# Connector.net
KiCad netlist of a schematic drawn in Altium Designer
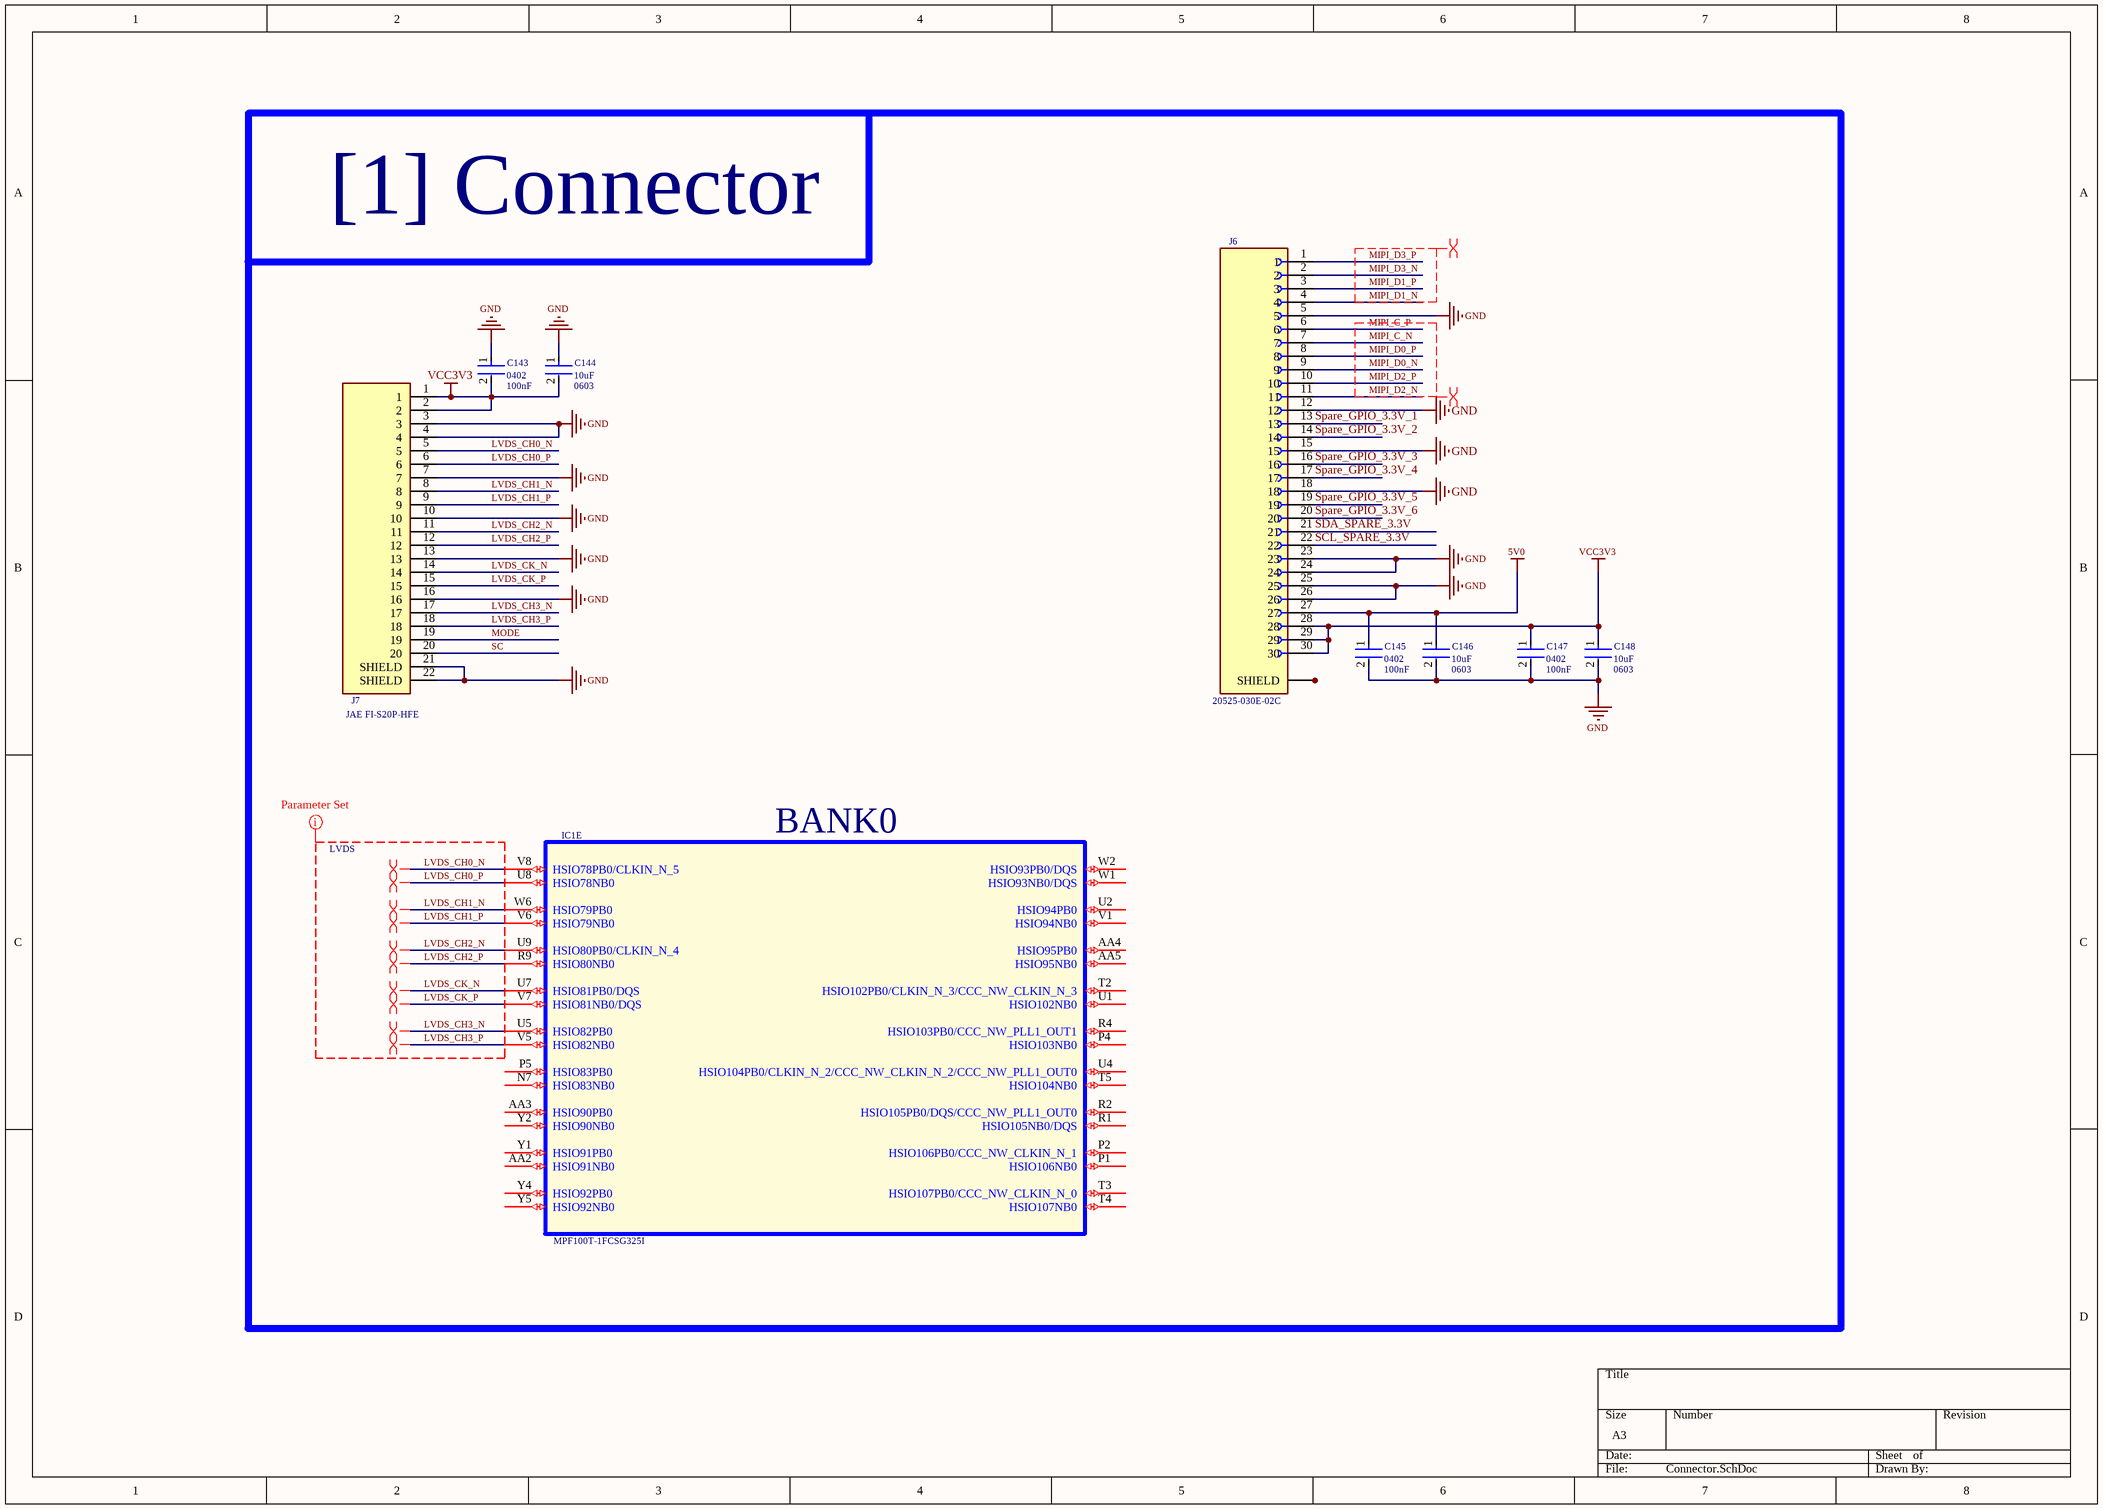
[diagram p0: Connector.SchDoc]

(export (version "E")
  (design (tool "Eeschema 10.0.6"))
  (components
    (comp (ref "C143")
      (value "C0402C104K8PACTU")
      (footprint "FP-C0402-BB-MFG")
      (description "CAP CER 0.1UF 10V X5R 0402")
      (fields
        (field (name "MANUFACTURER") "Kemet")
        (field (name "TOLERANCE") "0.1")
        (field (name "PACKAGE") "0402")
        (field (name "CAPACITANCE") "100nF")
      )
      (libsource (lib "Camera_PCB_proj") (part "CMP-2008-02046-2"))
    )
    (comp (ref "C144")
      (value "GRM188R60J106ME47D")
      (footprint "FP-GRM188-0_1-e0_2_0_55-IPC_A")
      (description "Chip Multilayer Ceramic Capacitors for General Purpose, 0603, 10uF, X5R, 15%, 20%, 6.3V")
      (fields
        (field (name "VOLTAGE") "6.3V")
        (field (name "TOLERANCE") "20%")
        (field (name "CAPACITANCE") "10uF")
        (field (name "CASE/PACKAGE") "0603")
      )
      (libsource (lib "Camera_PCB_proj") (part "CMP-2006-02792-2"))
    )
    (comp (ref "C145")
      (value "C0402C104K8PACTU")
      (footprint "FP-C0402-BB-MFG")
      (description "CAP CER 0.1UF 10V X5R 0402")
      (fields
        (field (name "MANUFACTURER") "Kemet")
        (field (name "TOLERANCE") "0.1")
        (field (name "PACKAGE") "0402")
        (field (name "CAPACITANCE") "100nF")
      )
      (libsource (lib "Camera_PCB_proj") (part "CMP-2008-02046-2"))
    )
    (comp (ref "C146")
      (value "GRM188R60J106ME47D")
      (footprint "FP-GRM188-0_1-e0_2_0_55-IPC_A")
      (description "Chip Multilayer Ceramic Capacitors for General Purpose, 0603, 10uF, X5R, 15%, 20%, 6.3V")
      (fields
        (field (name "VOLTAGE") "6.3V")
        (field (name "TOLERANCE") "20%")
        (field (name "CAPACITANCE") "10uF")
        (field (name "CASE/PACKAGE") "0603")
      )
      (libsource (lib "Camera_PCB_proj") (part "CMP-2006-02792-2"))
    )
    (comp (ref "C147")
      (value "C0402C104K8PACTU")
      (footprint "FP-C0402-BB-MFG")
      (description "CAP CER 0.1UF 10V X5R 0402")
      (fields
        (field (name "MANUFACTURER") "Kemet")
        (field (name "TOLERANCE") "0.1")
        (field (name "PACKAGE") "0402")
        (field (name "CAPACITANCE") "100nF")
      )
      (libsource (lib "Camera_PCB_proj") (part "CMP-2008-02046-2"))
    )
    (comp (ref "C148")
      (value "GRM188R60J106ME47D")
      (footprint "FP-GRM188-0_1-e0_2_0_55-IPC_A")
      (description "Chip Multilayer Ceramic Capacitors for General Purpose, 0603, 10uF, X5R, 15%, 20%, 6.3V")
      (fields
        (field (name "VOLTAGE") "6.3V")
        (field (name "TOLERANCE") "20%")
        (field (name "CAPACITANCE") "10uF")
        (field (name "CASE/PACKAGE") "0603")
      )
      (libsource (lib "Camera_PCB_proj") (part "CMP-2006-02792-2"))
    )
    (comp (ref "IC1")
      (value "MPF100T-1FCSG325I")
      (footprint "MPF100T-1FCSG325I")
      (fields (field (name "PART_NUMBER") "J00001"))
      (libsource (lib "PCB_Display_Doru") (part "MPF100T-1FCSG325I"))
    )
    (comp (ref "J6")
      (value "20525-030E-02C")
      (footprint "I-PEX_20525-030E-02C")
      (description "0.4 mm pitch, Horizontal mating Micro-coaxial cable connector")
      (fields (field (name "MF") "I-PEX"))
      (libsource (lib "Camera_PCB_proj") (part "20525-030E-02C"))
    )
    (comp (ref "J7")
      (value "JAE FI-S20P-HFE")
      (footprint "JAE FI-S20P-HFE")
      (fields (field (name "PART_NUMBER") "J00001"))
      (libsource (lib "PCB_Display_Doru") (part "JAE FI-S20P-HFE"))
    )
  )
  (nets
    (net (code "1") (name "/LVDS_CH0_N") (class "Default")
      (node (ref "IC1") (pin "V8") (pinfunction "HSIO78PB0/CLKIN_N_5_V8") (pintype "bidirectional"))
      (node (ref "J7") (pin "5") (pinfunction "5_5") (pintype "passive"))
    )
    (net (code "2") (name "/LVDS_CH0_P") (class "Default")
      (node (ref "IC1") (pin "U8") (pinfunction "HSIO78NB0_U8") (pintype "bidirectional"))
      (node (ref "J7") (pin "6") (pinfunction "6_6") (pintype "passive"))
    )
    (net (code "3") (name "/LVDS_CH1_N") (class "Default")
      (node (ref "IC1") (pin "W6") (pinfunction "HSIO79PB0_W6") (pintype "bidirectional"))
      (node (ref "J7") (pin "8") (pinfunction "8_8") (pintype "passive"))
    )
    (net (code "4") (name "/LVDS_CH1_P") (class "Default")
      (node (ref "IC1") (pin "V6") (pinfunction "HSIO79NB0_V6") (pintype "bidirectional"))
      (node (ref "J7") (pin "9") (pinfunction "9_9") (pintype "passive"))
    )
    (net (code "5") (name "/LVDS_CH2_N") (class "Default")
      (node (ref "IC1") (pin "U9") (pinfunction "HSIO80PB0/CLKIN_N_4_U9") (pintype "bidirectional"))
      (node (ref "J7") (pin "11") (pinfunction "11_11") (pintype "passive"))
    )
    (net (code "6") (name "/LVDS_CH2_P") (class "Default")
      (node (ref "IC1") (pin "R9") (pinfunction "HSIO80NB0_R9") (pintype "bidirectional"))
      (node (ref "J7") (pin "12") (pinfunction "12_12") (pintype "passive"))
    )
    (net (code "7") (name "/LVDS_CH3_N") (class "Default")
      (node (ref "IC1") (pin "U5") (pinfunction "HSIO82PB0_U5") (pintype "bidirectional"))
      (node (ref "J7") (pin "17") (pinfunction "17_17") (pintype "passive"))
    )
    (net (code "8") (name "/LVDS_CH3_P") (class "Default")
      (node (ref "IC1") (pin "V5") (pinfunction "HSIO82NB0_V5") (pintype "bidirectional"))
      (node (ref "J7") (pin "18") (pinfunction "18_18") (pintype "passive"))
    )
    (net (code "9") (name "/LVDS_CK_N") (class "Default")
      (node (ref "IC1") (pin "U7") (pinfunction "HSIO81PB0/DQS_U7") (pintype "bidirectional"))
      (node (ref "J7") (pin "14") (pinfunction "14_14") (pintype "passive"))
    )
    (net (code "10") (name "/LVDS_CK_P") (class "Default")
      (node (ref "IC1") (pin "V7") (pinfunction "HSIO81NB0/DQS_V7") (pintype "bidirectional"))
      (node (ref "J7") (pin "15") (pinfunction "15_15") (pintype "passive"))
    )
    (net (code "11") (name "/MIPI_C_N") (class "Default")
      (node (ref "J6") (pin "7") (pinfunction "7_7") (pintype "passive"))
    )
    (net (code "12") (name "/MIPI_C_P") (class "Default")
      (node (ref "J6") (pin "6") (pinfunction "6_6") (pintype "passive"))
    )
    (net (code "13") (name "/MIPI_D0_N") (class "Default")
      (node (ref "J6") (pin "9") (pinfunction "9_9") (pintype "passive"))
    )
    (net (code "14") (name "/MIPI_D0_P") (class "Default")
      (node (ref "J6") (pin "8") (pinfunction "8_8") (pintype "passive"))
    )
    (net (code "15") (name "/MIPI_D1_N") (class "Default")
      (node (ref "J6") (pin "4") (pinfunction "4_4") (pintype "passive"))
    )
    (net (code "16") (name "/MIPI_D1_P") (class "Default")
      (node (ref "J6") (pin "3") (pinfunction "3_3") (pintype "passive"))
    )
    (net (code "17") (name "/MIPI_D2_N") (class "Default")
      (node (ref "J6") (pin "11") (pinfunction "11_11") (pintype "passive"))
    )
    (net (code "18") (name "/MIPI_D2_P") (class "Default")
      (node (ref "J6") (pin "10") (pinfunction "10_10") (pintype "passive"))
    )
    (net (code "19") (name "/MIPI_D3_N") (class "Default")
      (node (ref "J6") (pin "2") (pinfunction "2_2") (pintype "passive"))
    )
    (net (code "20") (name "/MIPI_D3_P") (class "Default")
      (node (ref "J6") (pin "1") (pinfunction "1_1") (pintype "passive"))
    )
    (net (code "21") (name "/MODE") (class "Default")
      (node (ref "J7") (pin "19") (pinfunction "19_19") (pintype "passive"))
    )
    (net (code "22") (name "/SC") (class "Default")
      (node (ref "J7") (pin "20") (pinfunction "20_20") (pintype "passive"))
    )
    (net (code "23") (name "/SCL_SPARE_3.3V") (class "Default")
      (node (ref "J6") (pin "22") (pinfunction "22_22") (pintype "passive"))
    )
    (net (code "24") (name "/SDA_SPARE_3.3V") (class "Default")
      (node (ref "J6") (pin "21") (pinfunction "21_21") (pintype "passive"))
    )
    (net (code "25") (name "/Spare_GPIO_3.3V_1") (class "Default")
      (node (ref "J6") (pin "13") (pinfunction "13_13") (pintype "passive"))
    )
    (net (code "26") (name "/Spare_GPIO_3.3V_2") (class "Default")
      (node (ref "J6") (pin "14") (pinfunction "14_14") (pintype "passive"))
    )
    (net (code "27") (name "/Spare_GPIO_3.3V_3") (class "Default")
      (node (ref "J6") (pin "16") (pinfunction "16_16") (pintype "passive"))
    )
    (net (code "28") (name "/Spare_GPIO_3.3V_4") (class "Default")
      (node (ref "J6") (pin "17") (pinfunction "17_17") (pintype "passive"))
    )
    (net (code "29") (name "/Spare_GPIO_3.3V_5") (class "Default")
      (node (ref "J6") (pin "19") (pinfunction "19_19") (pintype "passive"))
    )
    (net (code "30") (name "/Spare_GPIO_3.3V_6") (class "Default")
      (node (ref "J6") (pin "20") (pinfunction "20_20") (pintype "passive"))
    )
    (net (code "31") (name "5V0") (class "Default")
      (node (ref "C145") (pin "1") (pinfunction "1_1") (pintype "passive"))
      (node (ref "C146") (pin "1") (pinfunction "1_1") (pintype "passive"))
      (node (ref "J6") (pin "27") (pinfunction "27_27") (pintype "passive"))
    )
    (net (code "32") (name "GND") (class "Default")
      (node (ref "C143") (pin "1") (pinfunction "1_1") (pintype "passive"))
      (node (ref "C144") (pin "1") (pinfunction "1_1") (pintype "passive"))
      (node (ref "C145") (pin "2") (pinfunction "2_2") (pintype "passive"))
      (node (ref "C146") (pin "2") (pinfunction "2_2") (pintype "passive"))
      (node (ref "C147") (pin "2") (pinfunction "2_2") (pintype "passive"))
      (node (ref "C148") (pin "2") (pinfunction "2_2") (pintype "passive"))
      (node (ref "J6") (pin "12") (pinfunction "12_12") (pintype "passive"))
      (node (ref "J6") (pin "15") (pinfunction "15_15") (pintype "passive"))
      (node (ref "J6") (pin "18") (pinfunction "18_18") (pintype "passive"))
      (node (ref "J6") (pin "23") (pinfunction "23_23") (pintype "passive"))
      (node (ref "J6") (pin "24") (pinfunction "24_24") (pintype "passive"))
      (node (ref "J6") (pin "25") (pinfunction "25_25") (pintype "passive"))
      (node (ref "J6") (pin "26") (pinfunction "26_26") (pintype "passive"))
      (node (ref "J6") (pin "5") (pinfunction "5_5") (pintype "passive"))
      (node (ref "J7") (pin "10") (pinfunction "10_10") (pintype "passive"))
      (node (ref "J7") (pin "13") (pinfunction "13_13") (pintype "passive"))
      (node (ref "J7") (pin "16") (pinfunction "16_16") (pintype "passive"))
      (node (ref "J7") (pin "21") (pinfunction "SHIELD_21") (pintype "passive"))
      (node (ref "J7") (pin "22") (pinfunction "SHIELD_22") (pintype "passive"))
      (node (ref "J7") (pin "3") (pinfunction "3_3") (pintype "passive"))
      (node (ref "J7") (pin "4") (pinfunction "4_4") (pintype "passive"))
      (node (ref "J7") (pin "7") (pinfunction "7_7") (pintype "passive"))
    )
    (net (code "33") (name "Net-(J6-SHIELD-PadP1)") (class "Default")
      (node (ref "J6") (pin "P1") (pinfunction "SHIELD_P1") (pintype "passive"))
      (node (ref "J6") (pin "P10") (pinfunction "SHIELD_P10") (pintype "passive"))
      (node (ref "J6") (pin "P11") (pinfunction "SHIELD_P11") (pintype "passive"))
      (node (ref "J6") (pin "P2") (pinfunction "SHIELD_P2") (pintype "passive"))
      (node (ref "J6") (pin "P3") (pinfunction "SHIELD_P3") (pintype "passive"))
      (node (ref "J6") (pin "P4") (pinfunction "SHIELD_P4") (pintype "passive"))
      (node (ref "J6") (pin "P5") (pinfunction "SHIELD_P5") (pintype "passive"))
      (node (ref "J6") (pin "P6") (pinfunction "SHIELD_P6") (pintype "passive"))
      (node (ref "J6") (pin "P7") (pinfunction "SHIELD_P7") (pintype "passive"))
      (node (ref "J6") (pin "P8") (pinfunction "SHIELD_P8") (pintype "passive"))
      (node (ref "J6") (pin "P9") (pinfunction "SHIELD_P9") (pintype "passive"))
    )
    (net (code "34") (name "VCC3V3") (class "Default")
      (node (ref "C143") (pin "2") (pinfunction "2_2") (pintype "passive"))
      (node (ref "C144") (pin "2") (pinfunction "2_2") (pintype "passive"))
      (node (ref "C147") (pin "1") (pinfunction "1_1") (pintype "passive"))
      (node (ref "C148") (pin "1") (pinfunction "1_1") (pintype "passive"))
      (node (ref "J6") (pin "28") (pinfunction "28_28") (pintype "passive"))
      (node (ref "J6") (pin "29") (pinfunction "29_29") (pintype "passive"))
      (node (ref "J6") (pin "30") (pinfunction "30_30") (pintype "passive"))
      (node (ref "J7") (pin "1") (pinfunction "1_1") (pintype "passive"))
      (node (ref "J7") (pin "2") (pinfunction "2_2") (pintype "passive"))
    )
    (net (code "35") (name "unconnected-(IC1E-HSIO83NB0-PadN7)") (class "Default")
      (node (ref "IC1") (pin "N7") (pinfunction "HSIO83NB0_N7") (pintype "bidirectional"))
    )
    (net (code "36") (name "unconnected-(IC1E-HSIO83PB0-PadP5)") (class "Default")
      (node (ref "IC1") (pin "P5") (pinfunction "HSIO83PB0_P5") (pintype "bidirectional"))
    )
    (net (code "37") (name "unconnected-(IC1E-HSIO90NB0-PadY2)") (class "Default")
      (node (ref "IC1") (pin "Y2") (pinfunction "HSIO90NB0_Y2") (pintype "bidirectional"))
    )
    (net (code "38") (name "unconnected-(IC1E-HSIO90PB0-PadAA3)") (class "Default")
      (node (ref "IC1") (pin "AA3") (pinfunction "HSIO90PB0_AA3") (pintype "bidirectional"))
    )
    (net (code "39") (name "unconnected-(IC1E-HSIO91NB0-PadAA2)") (class "Default")
      (node (ref "IC1") (pin "AA2") (pinfunction "HSIO91NB0_AA2") (pintype "bidirectional"))
    )
    (net (code "40") (name "unconnected-(IC1E-HSIO91PB0-PadY1)") (class "Default")
      (node (ref "IC1") (pin "Y1") (pinfunction "HSIO91PB0_Y1") (pintype "bidirectional"))
    )
    (net (code "41") (name "unconnected-(IC1E-HSIO92NB0-PadY5)") (class "Default")
      (node (ref "IC1") (pin "Y5") (pinfunction "HSIO92NB0_Y5") (pintype "bidirectional"))
    )
    (net (code "42") (name "unconnected-(IC1E-HSIO92PB0-PadY4)") (class "Default")
      (node (ref "IC1") (pin "Y4") (pinfunction "HSIO92PB0_Y4") (pintype "bidirectional"))
    )
    (net (code "43") (name "unconnected-(IC1E-HSIO93NB0{slash}DQS-PadW1)") (class "Default")
      (node (ref "IC1") (pin "W1") (pinfunction "HSIO93NB0/DQS_W1") (pintype "bidirectional"))
    )
    (net (code "44") (name "unconnected-(IC1E-HSIO93PB0{slash}DQS-PadW2)") (class "Default")
      (node (ref "IC1") (pin "W2") (pinfunction "HSIO93PB0/DQS_W2") (pintype "bidirectional"))
    )
    (net (code "45") (name "unconnected-(IC1E-HSIO94NB0-PadV1)") (class "Default")
      (node (ref "IC1") (pin "V1") (pinfunction "HSIO94NB0_V1") (pintype "bidirectional"))
    )
    (net (code "46") (name "unconnected-(IC1E-HSIO94PB0-PadU2)") (class "Default")
      (node (ref "IC1") (pin "U2") (pinfunction "HSIO94PB0_U2") (pintype "bidirectional"))
    )
    (net (code "47") (name "unconnected-(IC1E-HSIO95NB0-PadAA5)") (class "Default")
      (node (ref "IC1") (pin "AA5") (pinfunction "HSIO95NB0_AA5") (pintype "bidirectional"))
    )
    (net (code "48") (name "unconnected-(IC1E-HSIO95PB0-PadAA4)") (class "Default")
      (node (ref "IC1") (pin "AA4") (pinfunction "HSIO95PB0_AA4") (pintype "bidirectional"))
    )
    (net (code "49") (name "unconnected-(IC1E-HSIO102NB0-PadU1)") (class "Default")
      (node (ref "IC1") (pin "U1") (pinfunction "HSIO102NB0_U1") (pintype "bidirectional"))
    )
    (net (code "50") (name "unconnected-(IC1E-HSIO102PB0{slash}CLKIN_N_3{slash}CCC_NW_CLKIN_N_3-PadT2)") (class "Default")
      (node (ref "IC1") (pin "T2") (pinfunction "HSIO102PB0/CLKIN_N_3/CCC_NW_CLKIN_N_3_T2") (pintype "bidirectional"))
    )
    (net (code "51") (name "unconnected-(IC1E-HSIO103NB0-PadP4)") (class "Default")
      (node (ref "IC1") (pin "P4") (pinfunction "HSIO103NB0_P4") (pintype "bidirectional"))
    )
    (net (code "52") (name "unconnected-(IC1E-HSIO103PB0{slash}CCC_NW_PLL1_OUT1-PadR4)") (class "Default")
      (node (ref "IC1") (pin "R4") (pinfunction "HSIO103PB0/CCC_NW_PLL1_OUT1_R4") (pintype "bidirectional"))
    )
    (net (code "53") (name "unconnected-(IC1E-HSIO104NB0-PadT5)") (class "Default")
      (node (ref "IC1") (pin "T5") (pinfunction "HSIO104NB0_T5") (pintype "bidirectional"))
    )
    (net (code "54") (name "unconnected-(IC1E-HSIO104PB0{slash}CLKIN_N_2{slash}CCC_NW_CLKIN_N_2{slash}CCC_NW_PLL1_OUT0-PadU4)") (class "Default")
      (node (ref "IC1") (pin "U4") (pinfunction "HSIO104PB0/CLKIN_N_2/CCC_NW_CLKIN_N_2/CCC_NW_PLL1_OUT0_U4") (pintype "bidirectional"))
    )
    (net (code "55") (name "unconnected-(IC1E-HSIO105NB0{slash}DQS-PadR1)") (class "Default")
      (node (ref "IC1") (pin "R1") (pinfunction "HSIO105NB0/DQS_R1") (pintype "bidirectional"))
    )
    (net (code "56") (name "unconnected-(IC1E-HSIO105PB0{slash}DQS{slash}CCC_NW_PLL1_OUT0-PadR2)") (class "Default")
      (node (ref "IC1") (pin "R2") (pinfunction "HSIO105PB0/DQS/CCC_NW_PLL1_OUT0_R2") (pintype "bidirectional"))
    )
    (net (code "57") (name "unconnected-(IC1E-HSIO106NB0-PadP1)") (class "Default")
      (node (ref "IC1") (pin "P1") (pinfunction "HSIO106NB0_P1") (pintype "bidirectional"))
    )
    (net (code "58") (name "unconnected-(IC1E-HSIO106PB0{slash}CCC_NW_CLKIN_N_1-PadP2)") (class "Default")
      (node (ref "IC1") (pin "P2") (pinfunction "HSIO106PB0/CCC_NW_CLKIN_N_1_P2") (pintype "bidirectional"))
    )
    (net (code "59") (name "unconnected-(IC1E-HSIO107NB0-PadT4)") (class "Default")
      (node (ref "IC1") (pin "T4") (pinfunction "HSIO107NB0_T4") (pintype "bidirectional"))
    )
    (net (code "60") (name "unconnected-(IC1E-HSIO107PB0{slash}CCC_NW_CLKIN_N_0-PadT3)") (class "Default")
      (node (ref "IC1") (pin "T3") (pinfunction "HSIO107PB0/CCC_NW_CLKIN_N_0_T3") (pintype "bidirectional"))
    )
  )
)
